# Main.net
KiCad netlist of a schematic drawn in Altium Designer
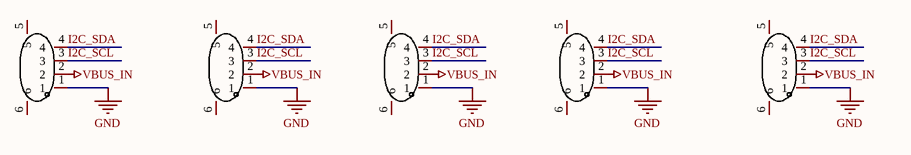
[diagram p0: Main.SchDoc]

(export (version "E")
  (design (tool "Eeschema 10.0.6"))
  (components
    (comp (ref "FPC1")
      (value "0.5K-DX-4PWB")
      (footprint "FPC-SMD_4P-P0.50_DEALON_0.5K-DX-4PWB")
      (fields (field (name "MANUFACTURER") "HDGC(华德共创)"))
      (libsource (lib "altium-import") (part "root_2_0.5K-DX-4PWB_"))
    )
    (comp (ref "FPC2")
      (value "0.5K-DX-4PWB")
      (footprint "FPC-SMD_4P-P0.50_DEALON_0.5K-DX-4PWB")
      (fields (field (name "MANUFACTURER") "HDGC(华德共创)"))
      (libsource (lib "altium-import") (part "root_2_0.5K-DX-4PWB_"))
    )
    (comp (ref "FPC3")
      (value "0.5K-DX-4PWB")
      (footprint "FPC-SMD_4P-P0.50_DEALON_0.5K-DX-4PWB")
      (fields (field (name "MANUFACTURER") "HDGC(华德共创)"))
      (libsource (lib "altium-import") (part "root_2_0.5K-DX-4PWB_"))
    )
    (comp (ref "FPC4")
      (value "0.5K-DX-4PWB")
      (footprint "FPC-SMD_4P-P0.50_DEALON_0.5K-DX-4PWB")
      (fields (field (name "MANUFACTURER") "HDGC(华德共创)"))
      (libsource (lib "altium-import") (part "root_2_0.5K-DX-4PWB_"))
    )
    (comp (ref "FPC5")
      (value "0.5K-DX-4PWB")
      (footprint "FPC-SMD_4P-P0.50_DEALON_0.5K-DX-4PWB")
      (fields (field (name "MANUFACTURER") "HDGC(华德共创)"))
      (libsource (lib "altium-import") (part "root_2_0.5K-DX-4PWB_"))
    )
  )
  (nets
    (net (code "1") (name "/I2C_SCL") (class "Default")
      (node (ref "FPC1") (pin "3") (pinfunction "3_3") (pintype "passive"))
      (node (ref "FPC2") (pin "3") (pinfunction "3_3") (pintype "passive"))
      (node (ref "FPC3") (pin "3") (pinfunction "3_3") (pintype "passive"))
      (node (ref "FPC4") (pin "3") (pinfunction "3_3") (pintype "passive"))
      (node (ref "FPC5") (pin "3") (pinfunction "3_3") (pintype "passive"))
    )
    (net (code "2") (name "/I2C_SDA") (class "Default")
      (node (ref "FPC1") (pin "4") (pinfunction "4_4") (pintype "passive"))
      (node (ref "FPC2") (pin "4") (pinfunction "4_4") (pintype "passive"))
      (node (ref "FPC3") (pin "4") (pinfunction "4_4") (pintype "passive"))
      (node (ref "FPC4") (pin "4") (pinfunction "4_4") (pintype "passive"))
      (node (ref "FPC5") (pin "4") (pinfunction "4_4") (pintype "passive"))
    )
    (net (code "3") (name "GND") (class "Default")
      (node (ref "FPC1") (pin "1") (pinfunction "1_1") (pintype "passive"))
      (node (ref "FPC2") (pin "1") (pinfunction "1_1") (pintype "passive"))
      (node (ref "FPC3") (pin "1") (pinfunction "1_1") (pintype "passive"))
      (node (ref "FPC4") (pin "1") (pinfunction "1_1") (pintype "passive"))
      (node (ref "FPC5") (pin "1") (pinfunction "1_1") (pintype "passive"))
    )
    (net (code "4") (name "VBUS_IN") (class "Default")
      (node (ref "FPC1") (pin "2") (pinfunction "2_2") (pintype "passive"))
      (node (ref "FPC2") (pin "2") (pinfunction "2_2") (pintype "passive"))
      (node (ref "FPC3") (pin "2") (pinfunction "2_2") (pintype "passive"))
      (node (ref "FPC4") (pin "2") (pinfunction "2_2") (pintype "passive"))
      (node (ref "FPC5") (pin "2") (pinfunction "2_2") (pintype "passive"))
    )
    (net (code "5") (name "unconnected-(FPC1-Pad5)") (class "Default")
      (node (ref "FPC1") (pin "5") (pinfunction "5_5") (pintype "passive"))
    )
    (net (code "6") (name "unconnected-(FPC1-Pad6)") (class "Default")
      (node (ref "FPC1") (pin "6") (pinfunction "6_6") (pintype "passive"))
    )
    (net (code "7") (name "unconnected-(FPC2-Pad5)") (class "Default")
      (node (ref "FPC2") (pin "5") (pinfunction "5_5") (pintype "passive"))
    )
    (net (code "8") (name "unconnected-(FPC2-Pad6)") (class "Default")
      (node (ref "FPC2") (pin "6") (pinfunction "6_6") (pintype "passive"))
    )
    (net (code "9") (name "unconnected-(FPC3-Pad5)") (class "Default")
      (node (ref "FPC3") (pin "5") (pinfunction "5_5") (pintype "passive"))
    )
    (net (code "10") (name "unconnected-(FPC3-Pad6)") (class "Default")
      (node (ref "FPC3") (pin "6") (pinfunction "6_6") (pintype "passive"))
    )
    (net (code "11") (name "unconnected-(FPC4-Pad5)") (class "Default")
      (node (ref "FPC4") (pin "5") (pinfunction "5_5") (pintype "passive"))
    )
    (net (code "12") (name "unconnected-(FPC4-Pad6)") (class "Default")
      (node (ref "FPC4") (pin "6") (pinfunction "6_6") (pintype "passive"))
    )
    (net (code "13") (name "unconnected-(FPC5-Pad5)") (class "Default")
      (node (ref "FPC5") (pin "5") (pinfunction "5_5") (pintype "passive"))
    )
    (net (code "14") (name "unconnected-(FPC5-Pad6)") (class "Default")
      (node (ref "FPC5") (pin "6") (pinfunction "6_6") (pintype "passive"))
    )
  )
)
